# Pi_FPGA.net
KiCad netlist of a schematic drawn in Altium Designer
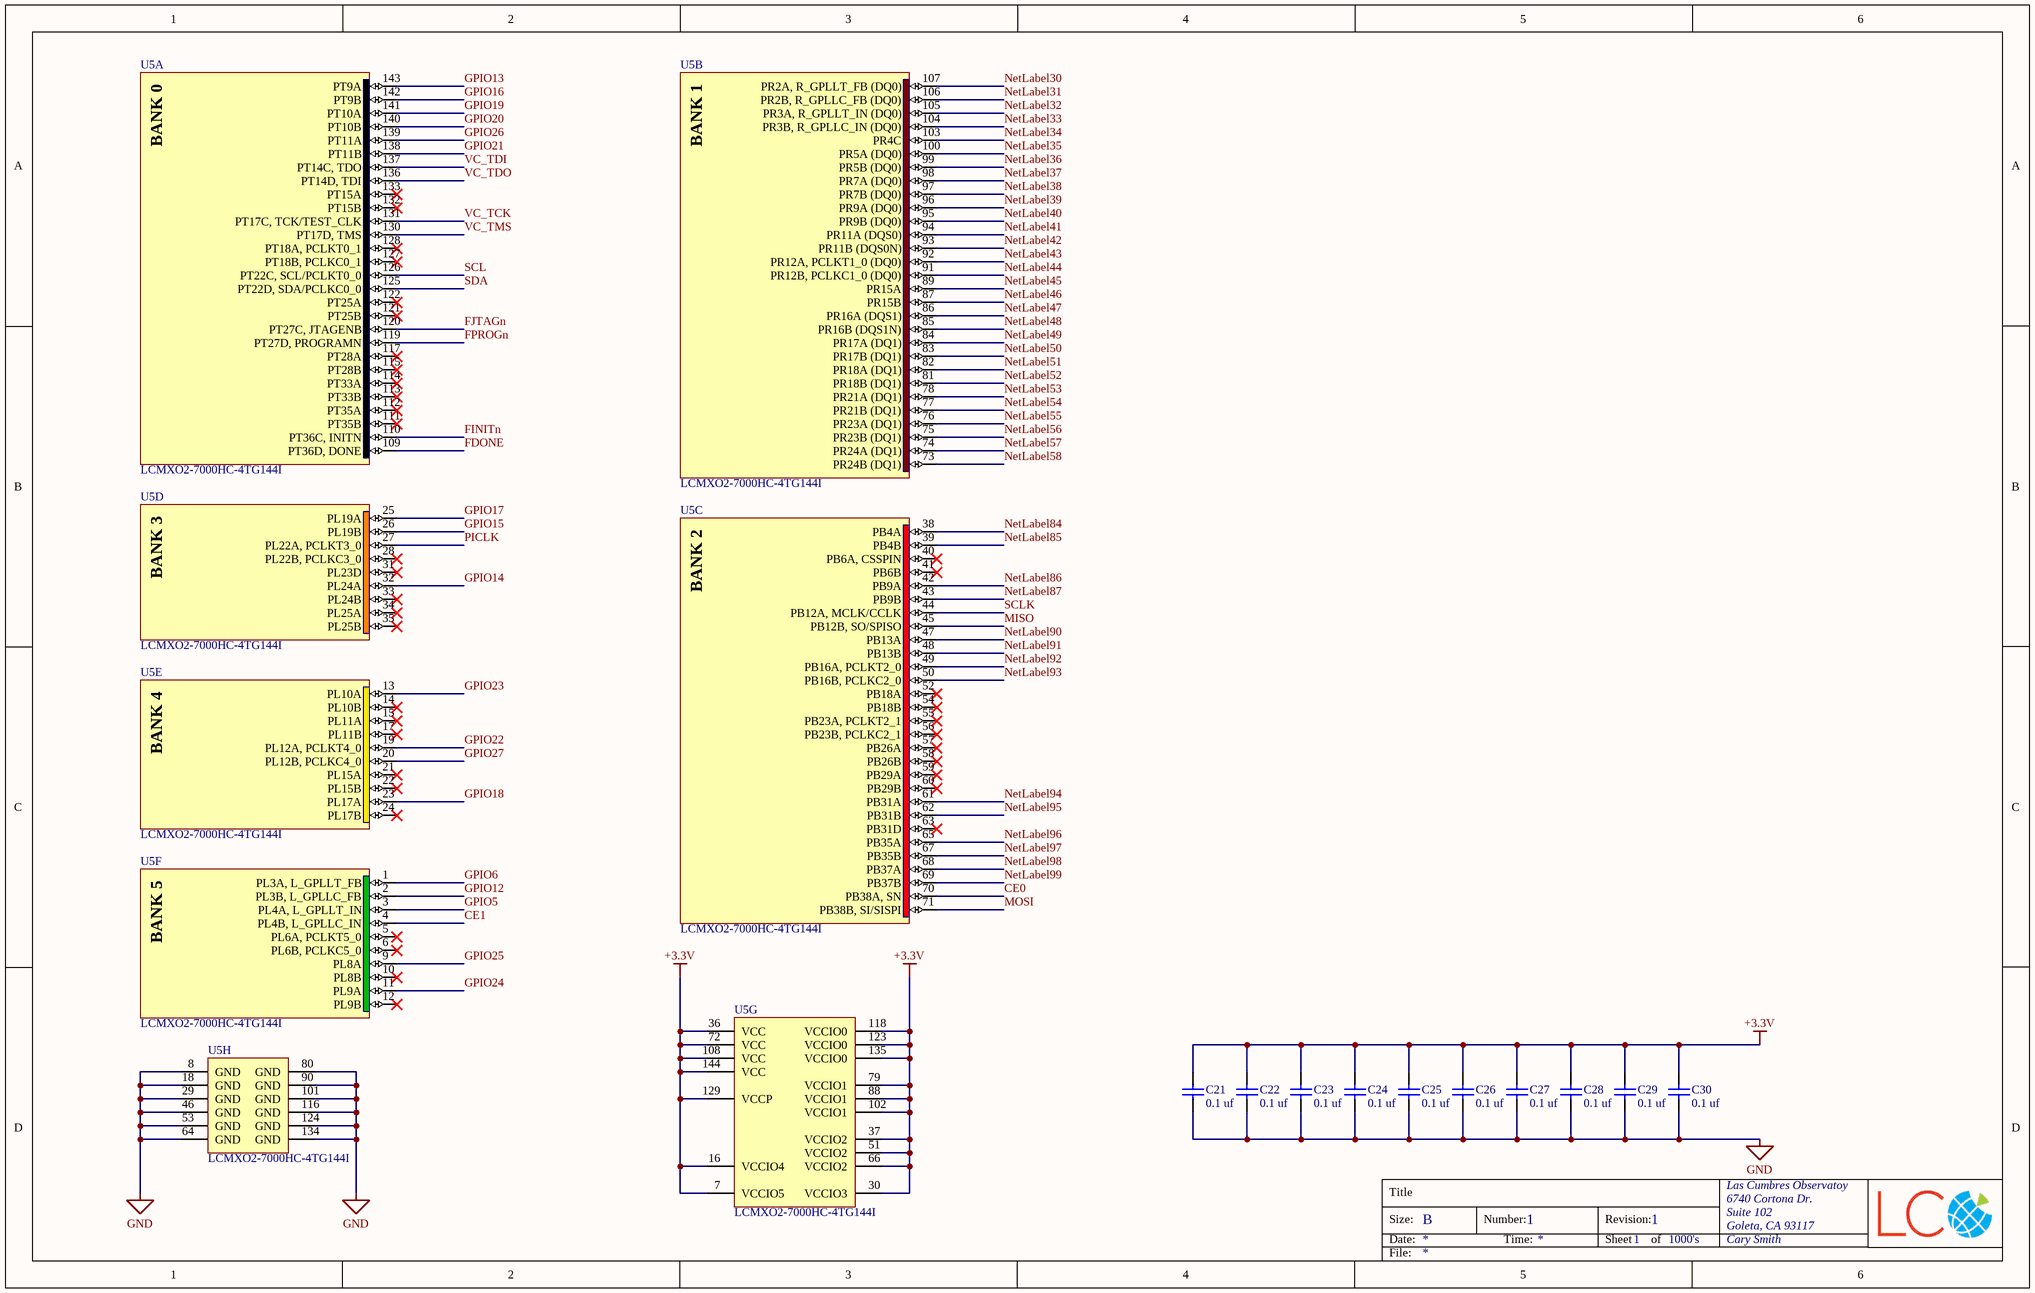
[diagram p0: Pi_FPGA.SchDoc]

(export (version "E")
  (design (tool "Eeschema 10.0.6"))
  (components
    (comp (ref "C21")
      (value "0.1 uf")
      (footprint "CAPC1608X92X38LL15T08")
      (description "VJ0603Y104KNXAO")
      (fields (field (name "MANUFACTURER") "Vitramon"))
      (libsource (lib "Altium Content Vault") (part "CAP"))
    )
    (comp (ref "C22")
      (value "0.1 uf")
      (footprint "CAPC1608X92X38LL15T08")
      (description "VJ0603Y104KNXAO")
      (fields (field (name "MANUFACTURER") "Vitramon"))
      (libsource (lib "Altium Content Vault") (part "CAP"))
    )
    (comp (ref "C23")
      (value "0.1 uf")
      (footprint "CAPC1608X92X38LL15T08")
      (description "VJ0603Y104KNXAO")
      (fields (field (name "MANUFACTURER") "Vitramon"))
      (libsource (lib "Altium Content Vault") (part "CAP"))
    )
    (comp (ref "C24")
      (value "0.1 uf")
      (footprint "CAPC1608X92X38LL15T08")
      (description "VJ0603Y104KNXAO")
      (fields (field (name "MANUFACTURER") "Vitramon"))
      (libsource (lib "Altium Content Vault") (part "CAP"))
    )
    (comp (ref "C25")
      (value "0.1 uf")
      (footprint "CAPC1608X92X38LL15T08")
      (description "VJ0603Y104KNXAO")
      (fields (field (name "MANUFACTURER") "Vitramon"))
      (libsource (lib "Altium Content Vault") (part "CAP"))
    )
    (comp (ref "C26")
      (value "0.1 uf")
      (footprint "CAPC1608X92X38LL15T08")
      (description "VJ0603Y104KNXAO")
      (fields (field (name "MANUFACTURER") "Vitramon"))
      (libsource (lib "Altium Content Vault") (part "CAP"))
    )
    (comp (ref "C27")
      (value "0.1 uf")
      (footprint "CAPC1608X92X38LL15T08")
      (description "VJ0603Y104KNXAO")
      (fields (field (name "MANUFACTURER") "Vitramon"))
      (libsource (lib "Altium Content Vault") (part "CAP"))
    )
    (comp (ref "C28")
      (value "0.1 uf")
      (footprint "CAPC1608X92X38LL15T08")
      (description "VJ0603Y104KNXAO")
      (fields (field (name "MANUFACTURER") "Vitramon"))
      (libsource (lib "Altium Content Vault") (part "CAP"))
    )
    (comp (ref "C29")
      (value "0.1 uf")
      (footprint "CAPC1608X92X38LL15T08")
      (description "VJ0603Y104KNXAO")
      (fields (field (name "MANUFACTURER") "Vitramon"))
      (libsource (lib "Altium Content Vault") (part "CAP"))
    )
    (comp (ref "C30")
      (value "0.1 uf")
      (footprint "CAPC1608X92X38LL15T08")
      (description "VJ0603Y104KNXAO")
      (fields (field (name "MANUFACTURER") "Vitramon"))
      (libsource (lib "Altium Content Vault") (part "CAP"))
    )
    (comp (ref "U5")
      (value "LCMXO2-7000HC-4TG144I")
      (footprint "TQFP144_N")
      (libsource (lib "Altium Content Vault") (part "PLD-LTMXO2-7000-TQ144"))
    )
  )
  (nets
    (net (code "1") (name "+3.3V") (class "Default")
      (node (ref "C21") (pin "2") (pinfunction "2_2") (pintype "passive"))
      (node (ref "C22") (pin "2") (pinfunction "2_2") (pintype "passive"))
      (node (ref "C23") (pin "2") (pinfunction "2_2") (pintype "passive"))
      (node (ref "C24") (pin "2") (pinfunction "2_2") (pintype "passive"))
      (node (ref "C25") (pin "2") (pinfunction "2_2") (pintype "passive"))
      (node (ref "C26") (pin "2") (pinfunction "2_2") (pintype "passive"))
      (node (ref "C27") (pin "2") (pinfunction "2_2") (pintype "passive"))
      (node (ref "C28") (pin "2") (pinfunction "2_2") (pintype "passive"))
      (node (ref "C29") (pin "2") (pinfunction "2_2") (pintype "passive"))
      (node (ref "C30") (pin "2") (pinfunction "2_2") (pintype "passive"))
      (node (ref "U5") (pin "102") (pinfunction "VCCIO1_102") (pintype "power_in"))
      (node (ref "U5") (pin "108") (pinfunction "VCC_108") (pintype "power_in"))
      (node (ref "U5") (pin "118") (pinfunction "VCCIO0_118") (pintype "power_in"))
      (node (ref "U5") (pin "123") (pinfunction "VCCIO0_123") (pintype "power_in"))
      (node (ref "U5") (pin "129") (pinfunction "VCCP_129") (pintype "power_in"))
      (node (ref "U5") (pin "135") (pinfunction "VCCIO0_135") (pintype "power_in"))
      (node (ref "U5") (pin "144") (pinfunction "VCC_144") (pintype "power_in"))
      (node (ref "U5") (pin "16") (pinfunction "VCCIO4_16") (pintype "power_in"))
      (node (ref "U5") (pin "30") (pinfunction "VCCIO3_30") (pintype "power_in"))
      (node (ref "U5") (pin "36") (pinfunction "VCC_36") (pintype "power_in"))
      (node (ref "U5") (pin "37") (pinfunction "VCCIO2_37") (pintype "power_in"))
      (node (ref "U5") (pin "51") (pinfunction "VCCIO2_51") (pintype "power_in"))
      (node (ref "U5") (pin "66") (pinfunction "VCCIO2_66") (pintype "power_in"))
      (node (ref "U5") (pin "7") (pinfunction "VCCIO5_7") (pintype "power_in"))
      (node (ref "U5") (pin "72") (pinfunction "VCC_72") (pintype "power_in"))
      (node (ref "U5") (pin "79") (pinfunction "VCCIO1_79") (pintype "power_in"))
      (node (ref "U5") (pin "88") (pinfunction "VCCIO1_88") (pintype "power_in"))
    )
    (net (code "2") (name "/CE0") (class "Default")
      (node (ref "U5") (pin "70") (pinfunction "PB38A,_SN_70") (pintype "bidirectional"))
    )
    (net (code "3") (name "/CE1") (class "Default")
      (node (ref "U5") (pin "4") (pinfunction "PL4B,_L_GPLLC_IN_4") (pintype "bidirectional"))
    )
    (net (code "4") (name "/FDONE") (class "Default")
      (node (ref "U5") (pin "109") (pinfunction "PT36D,_DONE_109") (pintype "bidirectional"))
    )
    (net (code "5") (name "/FINITn") (class "Default")
      (node (ref "U5") (pin "110") (pinfunction "PT36C,_INITN_110") (pintype "bidirectional"))
    )
    (net (code "6") (name "/FJTAGn") (class "Default")
      (node (ref "U5") (pin "120") (pinfunction "PT27C,_JTAGENB_120") (pintype "bidirectional"))
    )
    (net (code "7") (name "/FPROGn") (class "Default")
      (node (ref "U5") (pin "119") (pinfunction "PT27D,_PROGRAMN_119") (pintype "bidirectional"))
    )
    (net (code "8") (name "/GPIO5") (class "Default")
      (node (ref "U5") (pin "3") (pinfunction "PL4A,_L_GPLLT_IN_3") (pintype "bidirectional"))
    )
    (net (code "9") (name "/GPIO6") (class "Default")
      (node (ref "U5") (pin "1") (pinfunction "PL3A,_L_GPLLT_FB_1") (pintype "bidirectional"))
    )
    (net (code "10") (name "/GPIO12") (class "Default")
      (node (ref "U5") (pin "2") (pinfunction "PL3B,_L_GPLLC_FB_2") (pintype "bidirectional"))
    )
    (net (code "11") (name "/GPIO13") (class "Default")
      (node (ref "U5") (pin "143") (pinfunction "PT9A_143") (pintype "bidirectional"))
    )
    (net (code "12") (name "/GPIO14") (class "Default")
      (node (ref "U5") (pin "32") (pinfunction "PL24A_32") (pintype "bidirectional"))
    )
    (net (code "13") (name "/GPIO15") (class "Default")
      (node (ref "U5") (pin "26") (pinfunction "PL19B_26") (pintype "bidirectional"))
    )
    (net (code "14") (name "/GPIO16") (class "Default")
      (node (ref "U5") (pin "142") (pinfunction "PT9B_142") (pintype "bidirectional"))
    )
    (net (code "15") (name "/GPIO17") (class "Default")
      (node (ref "U5") (pin "25") (pinfunction "PL19A_25") (pintype "bidirectional"))
    )
    (net (code "16") (name "/GPIO18") (class "Default")
      (node (ref "U5") (pin "23") (pinfunction "PL17A_23") (pintype "bidirectional"))
    )
    (net (code "17") (name "/GPIO19") (class "Default")
      (node (ref "U5") (pin "141") (pinfunction "PT10A_141") (pintype "bidirectional"))
    )
    (net (code "18") (name "/GPIO20") (class "Default")
      (node (ref "U5") (pin "140") (pinfunction "PT10B_140") (pintype "bidirectional"))
    )
    (net (code "19") (name "/GPIO21") (class "Default")
      (node (ref "U5") (pin "138") (pinfunction "PT11B_138") (pintype "bidirectional"))
    )
    (net (code "20") (name "/GPIO22") (class "Default")
      (node (ref "U5") (pin "19") (pinfunction "PL12A,_PCLKT4_0_19") (pintype "bidirectional"))
    )
    (net (code "21") (name "/GPIO23") (class "Default")
      (node (ref "U5") (pin "13") (pinfunction "PL10A_13") (pintype "bidirectional"))
    )
    (net (code "22") (name "/GPIO24") (class "Default")
      (node (ref "U5") (pin "11") (pinfunction "PL9A_11") (pintype "bidirectional"))
    )
    (net (code "23") (name "/GPIO25") (class "Default")
      (node (ref "U5") (pin "9") (pinfunction "PL8A_9") (pintype "bidirectional"))
    )
    (net (code "24") (name "/GPIO26") (class "Default")
      (node (ref "U5") (pin "139") (pinfunction "PT11A_139") (pintype "bidirectional"))
    )
    (net (code "25") (name "/GPIO27") (class "Default")
      (node (ref "U5") (pin "20") (pinfunction "PL12B,_PCLKC4_0_20") (pintype "bidirectional"))
    )
    (net (code "26") (name "/MISO") (class "Default")
      (node (ref "U5") (pin "45") (pinfunction "PB12B,_SO/SPISO_45") (pintype "bidirectional"))
    )
    (net (code "27") (name "/MOSI") (class "Default")
      (node (ref "U5") (pin "71") (pinfunction "PB38B,_SI/SISPI_71") (pintype "bidirectional"))
    )
    (net (code "28") (name "/NetLabel30") (class "Default")
      (node (ref "U5") (pin "107") (pinfunction "PR2A,_R_GPLLT_FB_(DQ0)_107") (pintype "bidirectional"))
    )
    (net (code "29") (name "/NetLabel31") (class "Default")
      (node (ref "U5") (pin "106") (pinfunction "PR2B,_R_GPLLC_FB_(DQ0)_106") (pintype "bidirectional"))
    )
    (net (code "30") (name "/NetLabel32") (class "Default")
      (node (ref "U5") (pin "105") (pinfunction "PR3A,_R_GPLLT_IN_(DQ0)_105") (pintype "bidirectional"))
    )
    (net (code "31") (name "/NetLabel33") (class "Default")
      (node (ref "U5") (pin "104") (pinfunction "PR3B,_R_GPLLC_IN_(DQ0)_104") (pintype "bidirectional"))
    )
    (net (code "32") (name "/NetLabel34") (class "Default")
      (node (ref "U5") (pin "103") (pinfunction "PR4C_103") (pintype "bidirectional"))
    )
    (net (code "33") (name "/NetLabel35") (class "Default")
      (node (ref "U5") (pin "100") (pinfunction "PR5A_(DQ0)_100") (pintype "bidirectional"))
    )
    (net (code "34") (name "/NetLabel36") (class "Default")
      (node (ref "U5") (pin "99") (pinfunction "PR5B_(DQ0)_99") (pintype "bidirectional"))
    )
    (net (code "35") (name "/NetLabel37") (class "Default")
      (node (ref "U5") (pin "98") (pinfunction "PR7A_(DQ0)_98") (pintype "bidirectional"))
    )
    (net (code "36") (name "/NetLabel38") (class "Default")
      (node (ref "U5") (pin "97") (pinfunction "PR7B_(DQ0)_97") (pintype "bidirectional"))
    )
    (net (code "37") (name "/NetLabel39") (class "Default")
      (node (ref "U5") (pin "96") (pinfunction "PR9A_(DQ0)_96") (pintype "bidirectional"))
    )
    (net (code "38") (name "/NetLabel40") (class "Default")
      (node (ref "U5") (pin "95") (pinfunction "PR9B_(DQ0)_95") (pintype "bidirectional"))
    )
    (net (code "39") (name "/NetLabel41") (class "Default")
      (node (ref "U5") (pin "94") (pinfunction "PR11A_(DQS0)_94") (pintype "bidirectional"))
    )
    (net (code "40") (name "/NetLabel42") (class "Default")
      (node (ref "U5") (pin "93") (pinfunction "PR11B_(DQS0N)_93") (pintype "bidirectional"))
    )
    (net (code "41") (name "/NetLabel43") (class "Default")
      (node (ref "U5") (pin "92") (pinfunction "PR12A,_PCLKT1_0_(DQ0)_92") (pintype "bidirectional"))
    )
    (net (code "42") (name "/NetLabel44") (class "Default")
      (node (ref "U5") (pin "91") (pinfunction "PR12B,_PCLKC1_0_(DQ0)_91") (pintype "bidirectional"))
    )
    (net (code "43") (name "/NetLabel45") (class "Default")
      (node (ref "U5") (pin "89") (pinfunction "PR15A_89") (pintype "bidirectional"))
    )
    (net (code "44") (name "/NetLabel46") (class "Default")
      (node (ref "U5") (pin "87") (pinfunction "PR15B_87") (pintype "bidirectional"))
    )
    (net (code "45") (name "/NetLabel47") (class "Default")
      (node (ref "U5") (pin "86") (pinfunction "PR16A_(DQS1)_86") (pintype "bidirectional"))
    )
    (net (code "46") (name "/NetLabel48") (class "Default")
      (node (ref "U5") (pin "85") (pinfunction "PR16B_(DQS1N)_85") (pintype "bidirectional"))
    )
    (net (code "47") (name "/NetLabel49") (class "Default")
      (node (ref "U5") (pin "84") (pinfunction "PR17A_(DQ1)_84") (pintype "bidirectional"))
    )
    (net (code "48") (name "/NetLabel50") (class "Default")
      (node (ref "U5") (pin "83") (pinfunction "PR17B_(DQ1)_83") (pintype "bidirectional"))
    )
    (net (code "49") (name "/NetLabel51") (class "Default")
      (node (ref "U5") (pin "82") (pinfunction "PR18A_(DQ1)_82") (pintype "bidirectional"))
    )
    (net (code "50") (name "/NetLabel52") (class "Default")
      (node (ref "U5") (pin "81") (pinfunction "PR18B_(DQ1)_81") (pintype "bidirectional"))
    )
    (net (code "51") (name "/NetLabel53") (class "Default")
      (node (ref "U5") (pin "78") (pinfunction "PR21A_(DQ1)_78") (pintype "bidirectional"))
    )
    (net (code "52") (name "/NetLabel54") (class "Default")
      (node (ref "U5") (pin "77") (pinfunction "PR21B_(DQ1)_77") (pintype "bidirectional"))
    )
    (net (code "53") (name "/NetLabel55") (class "Default")
      (node (ref "U5") (pin "76") (pinfunction "PR23A_(DQ1)_76") (pintype "bidirectional"))
    )
    (net (code "54") (name "/NetLabel56") (class "Default")
      (node (ref "U5") (pin "75") (pinfunction "PR23B_(DQ1)_75") (pintype "bidirectional"))
    )
    (net (code "55") (name "/NetLabel57") (class "Default")
      (node (ref "U5") (pin "74") (pinfunction "PR24A_(DQ1)_74") (pintype "bidirectional"))
    )
    (net (code "56") (name "/NetLabel58") (class "Default")
      (node (ref "U5") (pin "73") (pinfunction "PR24B_(DQ1)_73") (pintype "bidirectional"))
    )
    (net (code "57") (name "/NetLabel84") (class "Default")
      (node (ref "U5") (pin "38") (pinfunction "PB4A_38") (pintype "bidirectional"))
    )
    (net (code "58") (name "/NetLabel85") (class "Default")
      (node (ref "U5") (pin "39") (pinfunction "PB4B_39") (pintype "bidirectional"))
    )
    (net (code "59") (name "/NetLabel86") (class "Default")
      (node (ref "U5") (pin "42") (pinfunction "PB9A_42") (pintype "bidirectional"))
    )
    (net (code "60") (name "/NetLabel87") (class "Default")
      (node (ref "U5") (pin "43") (pinfunction "PB9B_43") (pintype "bidirectional"))
    )
    (net (code "61") (name "/NetLabel90") (class "Default")
      (node (ref "U5") (pin "47") (pinfunction "PB13A_47") (pintype "bidirectional"))
    )
    (net (code "62") (name "/NetLabel91") (class "Default")
      (node (ref "U5") (pin "48") (pinfunction "PB13B_48") (pintype "bidirectional"))
    )
    (net (code "63") (name "/NetLabel92") (class "Default")
      (node (ref "U5") (pin "49") (pinfunction "PB16A,_PCLKT2_0_49") (pintype "bidirectional"))
    )
    (net (code "64") (name "/NetLabel93") (class "Default")
      (node (ref "U5") (pin "50") (pinfunction "PB16B,_PCLKC2_0_50") (pintype "bidirectional"))
    )
    (net (code "65") (name "/NetLabel94") (class "Default")
      (node (ref "U5") (pin "61") (pinfunction "PB31A_61") (pintype "bidirectional"))
    )
    (net (code "66") (name "/NetLabel95") (class "Default")
      (node (ref "U5") (pin "62") (pinfunction "PB31B_62") (pintype "bidirectional"))
    )
    (net (code "67") (name "/NetLabel96") (class "Default")
      (node (ref "U5") (pin "65") (pinfunction "PB35A_65") (pintype "bidirectional"))
    )
    (net (code "68") (name "/NetLabel97") (class "Default")
      (node (ref "U5") (pin "67") (pinfunction "PB35B_67") (pintype "bidirectional"))
    )
    (net (code "69") (name "/NetLabel98") (class "Default")
      (node (ref "U5") (pin "68") (pinfunction "PB37A_68") (pintype "bidirectional"))
    )
    (net (code "70") (name "/NetLabel99") (class "Default")
      (node (ref "U5") (pin "69") (pinfunction "PB37B_69") (pintype "bidirectional"))
    )
    (net (code "71") (name "/PICLK") (class "Default")
      (node (ref "U5") (pin "27") (pinfunction "PL22A,_PCLKT3_0_27") (pintype "bidirectional"))
    )
    (net (code "72") (name "/SCL") (class "Default")
      (node (ref "U5") (pin "126") (pinfunction "PT22C,_SCL/PCLKT0_0_126") (pintype "bidirectional"))
    )
    (net (code "73") (name "/SCLK") (class "Default")
      (node (ref "U5") (pin "44") (pinfunction "PB12A,_MCLK/CCLK_44") (pintype "bidirectional"))
    )
    (net (code "74") (name "/SDA") (class "Default")
      (node (ref "U5") (pin "125") (pinfunction "PT22D,_SDA/PCLKC0_0_125") (pintype "bidirectional"))
    )
    (net (code "75") (name "/VC_TCK") (class "Default")
      (node (ref "U5") (pin "131") (pinfunction "PT17C,_TCK/TEST_CLK_131") (pintype "bidirectional"))
    )
    (net (code "76") (name "/VC_TDI") (class "Default")
      (node (ref "U5") (pin "137") (pinfunction "PT14C,_TDO_137") (pintype "bidirectional"))
    )
    (net (code "77") (name "/VC_TDO") (class "Default")
      (node (ref "U5") (pin "136") (pinfunction "PT14D,_TDI_136") (pintype "bidirectional"))
    )
    (net (code "78") (name "/VC_TMS") (class "Default")
      (node (ref "U5") (pin "130") (pinfunction "PT17D,_TMS_130") (pintype "bidirectional"))
    )
    (net (code "79") (name "GND") (class "Default")
      (node (ref "C21") (pin "1") (pinfunction "1_1") (pintype "passive"))
      (node (ref "C22") (pin "1") (pinfunction "1_1") (pintype "passive"))
      (node (ref "C23") (pin "1") (pinfunction "1_1") (pintype "passive"))
      (node (ref "C24") (pin "1") (pinfunction "1_1") (pintype "passive"))
      (node (ref "C25") (pin "1") (pinfunction "1_1") (pintype "passive"))
      (node (ref "C26") (pin "1") (pinfunction "1_1") (pintype "passive"))
      (node (ref "C27") (pin "1") (pinfunction "1_1") (pintype "passive"))
      (node (ref "C28") (pin "1") (pinfunction "1_1") (pintype "passive"))
      (node (ref "C29") (pin "1") (pinfunction "1_1") (pintype "passive"))
      (node (ref "C30") (pin "1") (pinfunction "1_1") (pintype "passive"))
      (node (ref "U5") (pin "101") (pinfunction "GND_101") (pintype "power_in"))
      (node (ref "U5") (pin "116") (pinfunction "GND_116") (pintype "power_in"))
      (node (ref "U5") (pin "124") (pinfunction "GND_124") (pintype "power_in"))
      (node (ref "U5") (pin "134") (pinfunction "GND_134") (pintype "power_in"))
      (node (ref "U5") (pin "18") (pinfunction "GND_18") (pintype "power_in"))
      (node (ref "U5") (pin "29") (pinfunction "GND_29") (pintype "power_in"))
      (node (ref "U5") (pin "46") (pinfunction "GND_46") (pintype "power_in"))
      (node (ref "U5") (pin "53") (pinfunction "GND_53") (pintype "power_in"))
      (node (ref "U5") (pin "64") (pinfunction "GND_64") (pintype "power_in"))
      (node (ref "U5") (pin "8") (pinfunction "GND_8") (pintype "power_in"))
      (node (ref "U5") (pin "80") (pinfunction "GND_80") (pintype "power_in"))
      (node (ref "U5") (pin "90") (pinfunction "GND_90") (pintype "power_in"))
    )
    (net (code "80") (name "unconnected-(U5A-PT15A-Pad133)") (class "Default")
      (node (ref "U5") (pin "133") (pinfunction "PT15A_133") (pintype "bidirectional+no_connect"))
    )
    (net (code "81") (name "unconnected-(U5A-PT15B-Pad132)") (class "Default")
      (node (ref "U5") (pin "132") (pinfunction "PT15B_132") (pintype "bidirectional+no_connect"))
    )
    (net (code "82") (name "unconnected-(U5A-PT18A,_PCLKT0_1-Pad128)") (class "Default")
      (node (ref "U5") (pin "128") (pinfunction "PT18A,_PCLKT0_1_128") (pintype "bidirectional+no_connect"))
    )
    (net (code "83") (name "unconnected-(U5A-PT18B,_PCLKC0_1-Pad127)") (class "Default")
      (node (ref "U5") (pin "127") (pinfunction "PT18B,_PCLKC0_1_127") (pintype "bidirectional+no_connect"))
    )
    (net (code "84") (name "unconnected-(U5A-PT25A-Pad122)") (class "Default")
      (node (ref "U5") (pin "122") (pinfunction "PT25A_122") (pintype "bidirectional+no_connect"))
    )
    (net (code "85") (name "unconnected-(U5A-PT25B-Pad121)") (class "Default")
      (node (ref "U5") (pin "121") (pinfunction "PT25B_121") (pintype "bidirectional+no_connect"))
    )
    (net (code "86") (name "unconnected-(U5A-PT28A-Pad117)") (class "Default")
      (node (ref "U5") (pin "117") (pinfunction "PT28A_117") (pintype "bidirectional+no_connect"))
    )
    (net (code "87") (name "unconnected-(U5A-PT28B-Pad115)") (class "Default")
      (node (ref "U5") (pin "115") (pinfunction "PT28B_115") (pintype "bidirectional+no_connect"))
    )
    (net (code "88") (name "unconnected-(U5A-PT33A-Pad114)") (class "Default")
      (node (ref "U5") (pin "114") (pinfunction "PT33A_114") (pintype "bidirectional+no_connect"))
    )
    (net (code "89") (name "unconnected-(U5A-PT33B-Pad113)") (class "Default")
      (node (ref "U5") (pin "113") (pinfunction "PT33B_113") (pintype "bidirectional+no_connect"))
    )
    (net (code "90") (name "unconnected-(U5A-PT35A-Pad112)") (class "Default")
      (node (ref "U5") (pin "112") (pinfunction "PT35A_112") (pintype "bidirectional+no_connect"))
    )
    (net (code "91") (name "unconnected-(U5A-PT35B-Pad111)") (class "Default")
      (node (ref "U5") (pin "111") (pinfunction "PT35B_111") (pintype "bidirectional+no_connect"))
    )
    (net (code "92") (name "unconnected-(U5C-PB6A,_CSSPIN-Pad40)") (class "Default")
      (node (ref "U5") (pin "40") (pinfunction "PB6A,_CSSPIN_40") (pintype "bidirectional+no_connect"))
    )
    (net (code "93") (name "unconnected-(U5C-PB6B-Pad41)") (class "Default")
      (node (ref "U5") (pin "41") (pinfunction "PB6B_41") (pintype "bidirectional+no_connect"))
    )
    (net (code "94") (name "unconnected-(U5C-PB18A-Pad52)") (class "Default")
      (node (ref "U5") (pin "52") (pinfunction "PB18A_52") (pintype "bidirectional+no_connect"))
    )
    (net (code "95") (name "unconnected-(U5C-PB18B-Pad54)") (class "Default")
      (node (ref "U5") (pin "54") (pinfunction "PB18B_54") (pintype "bidirectional+no_connect"))
    )
    (net (code "96") (name "unconnected-(U5C-PB23A,_PCLKT2_1-Pad55)") (class "Default")
      (node (ref "U5") (pin "55") (pinfunction "PB23A,_PCLKT2_1_55") (pintype "bidirectional+no_connect"))
    )
    (net (code "97") (name "unconnected-(U5C-PB23B,_PCLKC2_1-Pad56)") (class "Default")
      (node (ref "U5") (pin "56") (pinfunction "PB23B,_PCLKC2_1_56") (pintype "bidirectional+no_connect"))
    )
    (net (code "98") (name "unconnected-(U5C-PB26A-Pad57)") (class "Default")
      (node (ref "U5") (pin "57") (pinfunction "PB26A_57") (pintype "bidirectional+no_connect"))
    )
    (net (code "99") (name "unconnected-(U5C-PB26B-Pad58)") (class "Default")
      (node (ref "U5") (pin "58") (pinfunction "PB26B_58") (pintype "bidirectional+no_connect"))
    )
    (net (code "100") (name "unconnected-(U5C-PB29A-Pad59)") (class "Default")
      (node (ref "U5") (pin "59") (pinfunction "PB29A_59") (pintype "bidirectional+no_connect"))
    )
    (net (code "101") (name "unconnected-(U5C-PB29B-Pad60)") (class "Default")
      (node (ref "U5") (pin "60") (pinfunction "PB29B_60") (pintype "bidirectional+no_connect"))
    )
    (net (code "102") (name "unconnected-(U5C-PB31D-Pad63)") (class "Default")
      (node (ref "U5") (pin "63") (pinfunction "PB31D_63") (pintype "bidirectional+no_connect"))
    )
    (net (code "103") (name "unconnected-(U5D-PL22B,_PCLKC3_0-Pad28)") (class "Default")
      (node (ref "U5") (pin "28") (pinfunction "PL22B,_PCLKC3_0_28") (pintype "bidirectional+no_connect"))
    )
    (net (code "104") (name "unconnected-(U5D-PL23D-Pad31)") (class "Default")
      (node (ref "U5") (pin "31") (pinfunction "PL23D_31") (pintype "bidirectional+no_connect"))
    )
    (net (code "105") (name "unconnected-(U5D-PL24B-Pad33)") (class "Default")
      (node (ref "U5") (pin "33") (pinfunction "PL24B_33") (pintype "bidirectional+no_connect"))
    )
    (net (code "106") (name "unconnected-(U5D-PL25A-Pad34)") (class "Default")
      (node (ref "U5") (pin "34") (pinfunction "PL25A_34") (pintype "bidirectional+no_connect"))
    )
    (net (code "107") (name "unconnected-(U5D-PL25B-Pad35)") (class "Default")
      (node (ref "U5") (pin "35") (pinfunction "PL25B_35") (pintype "bidirectional+no_connect"))
    )
    (net (code "108") (name "unconnected-(U5E-PL10B-Pad14)") (class "Default")
      (node (ref "U5") (pin "14") (pinfunction "PL10B_14") (pintype "bidirectional+no_connect"))
    )
    (net (code "109") (name "unconnected-(U5E-PL11A-Pad15)") (class "Default")
      (node (ref "U5") (pin "15") (pinfunction "PL11A_15") (pintype "bidirectional+no_connect"))
    )
    (net (code "110") (name "unconnected-(U5E-PL11B-Pad17)") (class "Default")
      (node (ref "U5") (pin "17") (pinfunction "PL11B_17") (pintype "bidirectional+no_connect"))
    )
    (net (code "111") (name "unconnected-(U5E-PL15A-Pad21)") (class "Default")
      (node (ref "U5") (pin "21") (pinfunction "PL15A_21") (pintype "bidirectional+no_connect"))
    )
    (net (code "112") (name "unconnected-(U5E-PL15B-Pad22)") (class "Default")
      (node (ref "U5") (pin "22") (pinfunction "PL15B_22") (pintype "bidirectional+no_connect"))
    )
    (net (code "113") (name "unconnected-(U5E-PL17B-Pad24)") (class "Default")
      (node (ref "U5") (pin "24") (pinfunction "PL17B_24") (pintype "bidirectional+no_connect"))
    )
    (net (code "114") (name "unconnected-(U5F-PL6A,_PCLKT5_0-Pad5)") (class "Default")
      (node (ref "U5") (pin "5") (pinfunction "PL6A,_PCLKT5_0_5") (pintype "bidirectional+no_connect"))
    )
    (net (code "115") (name "unconnected-(U5F-PL6B,_PCLKC5_0-Pad6)") (class "Default")
      (node (ref "U5") (pin "6") (pinfunction "PL6B,_PCLKC5_0_6") (pintype "bidirectional+no_connect"))
    )
    (net (code "116") (name "unconnected-(U5F-PL8B-Pad10)") (class "Default")
      (node (ref "U5") (pin "10") (pinfunction "PL8B_10") (pintype "bidirectional+no_connect"))
    )
    (net (code "117") (name "unconnected-(U5F-PL9B-Pad12)") (class "Default")
      (node (ref "U5") (pin "12") (pinfunction "PL9B_12") (pintype "bidirectional+no_connect"))
    )
  )
)
